# MicroMod-LoRa-1W-Function-Board.net
KiCad netlist of a schematic drawn in EAGLE
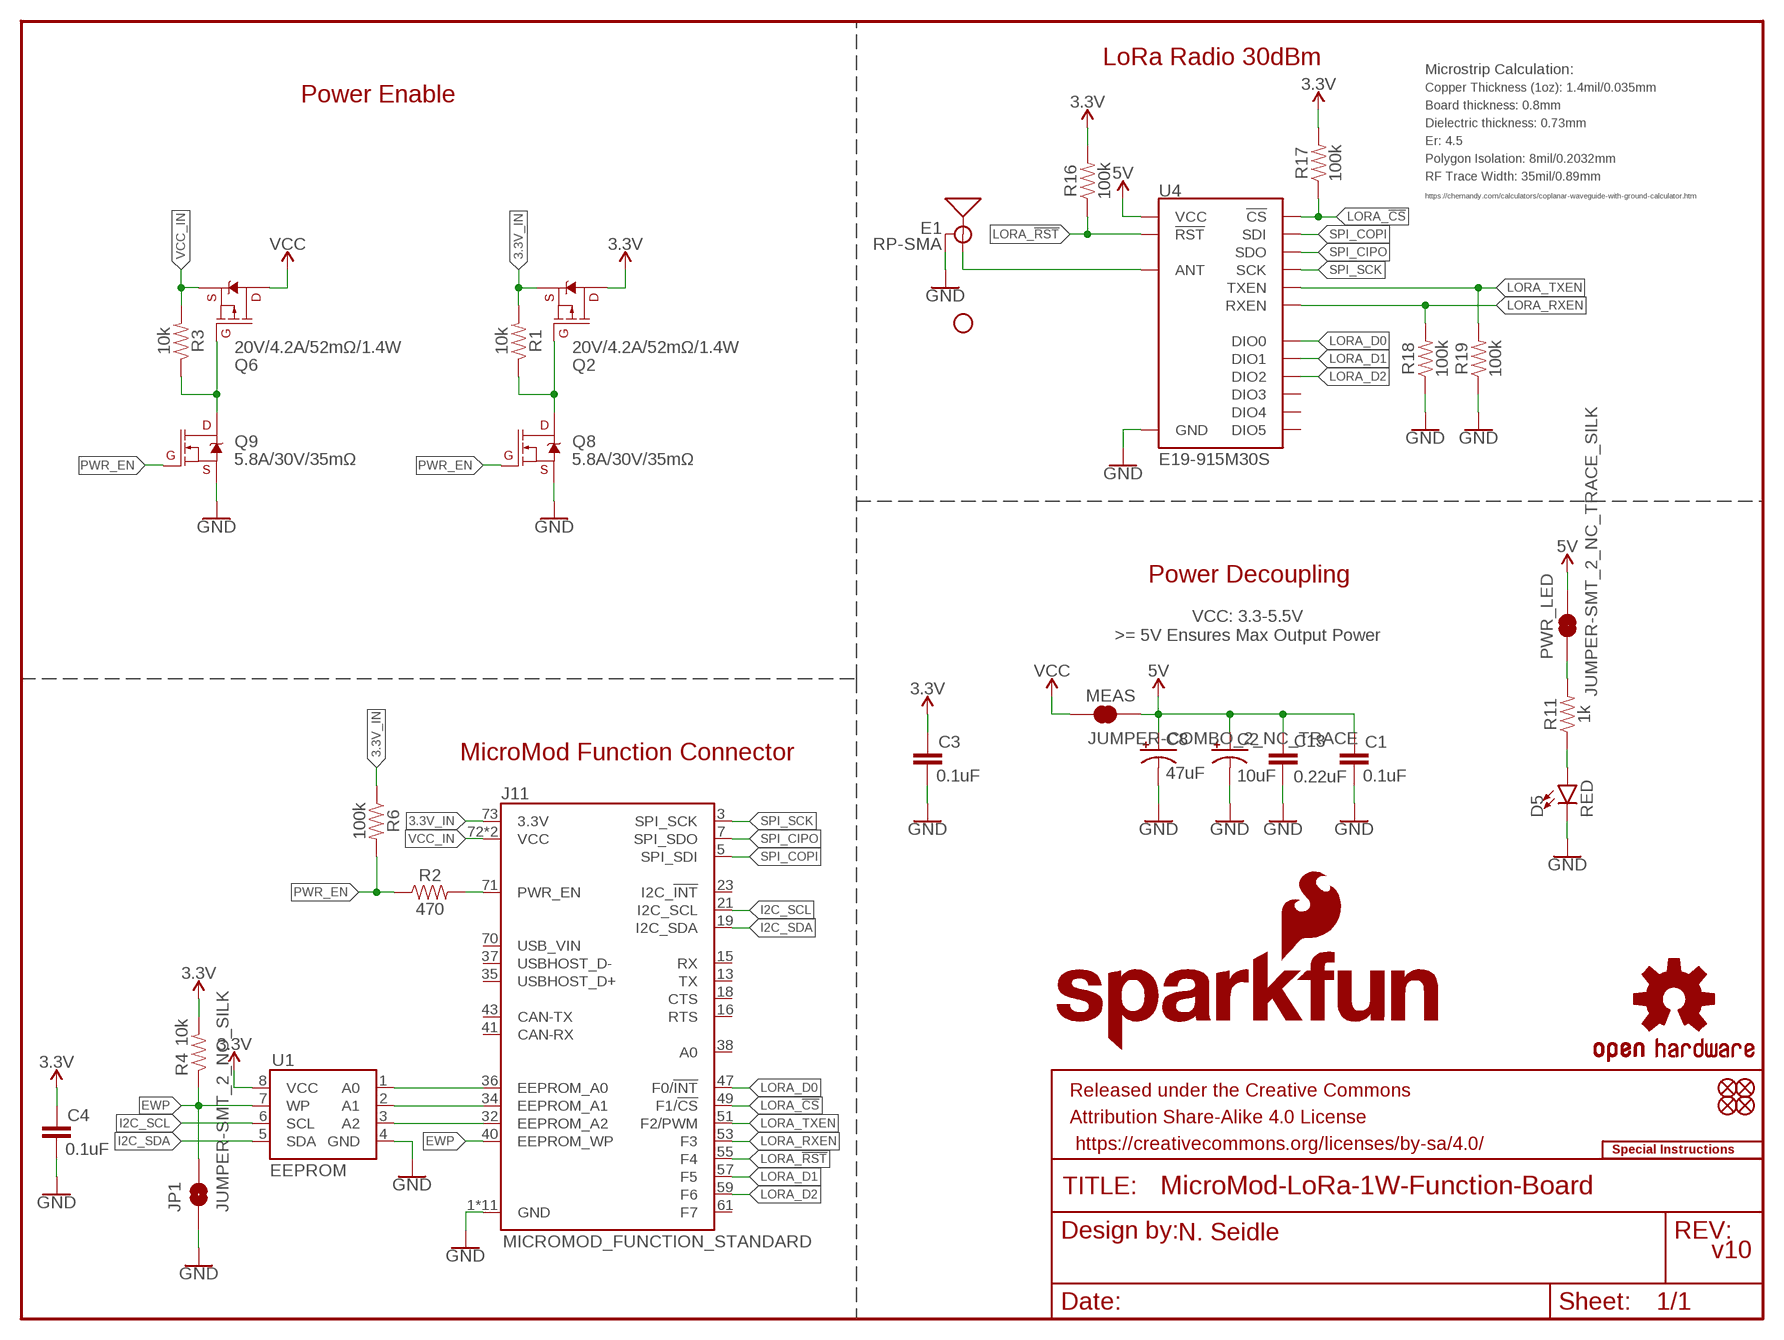
[diagram p0: schematic, sheet 1]

(export (version "E")
  (design (tool "Eeschema 10.0.6"))
  (components
    (comp (ref "C1")
      (value "0.1uF")
      (footprint "eagle-import:0603")
      (libsource (lib "eagle-import") (part "0.1UF-0603-25V-(+80/-20%)"))
    )
    (comp (ref "C2")
      (value "10uF")
      (footprint "eagle-import:EIA3216")
      (libsource (lib "eagle-import") (part "10UF-POLAR-EIA3216-16V-10%(TANT)"))
    )
    (comp (ref "C3")
      (value "0.1uF")
      (footprint "eagle-import:0603")
      (libsource (lib "eagle-import") (part "0.1UF-0603-25V-(+80/-20%)"))
    )
    (comp (ref "C4")
      (value "0.1uF")
      (footprint "eagle-import:0603")
      (libsource (lib "eagle-import") (part "0.1UF-0603-25V-(+80/-20%)"))
    )
    (comp (ref "C8")
      (value "47uF")
      (footprint "eagle-import:EIA3528")
      (libsource (lib "eagle-import") (part "47UF-POLAR-EIA3528-10V-10%"))
    )
    (comp (ref "C13")
      (value "0.22uF")
      (footprint "eagle-import:0603")
      (libsource (lib "eagle-import") (part "0.22UF-0603-25V-10%"))
    )
    (comp (ref "D5")
      (value "RED")
      (footprint "eagle-import:LED-0603")
      (libsource (lib "eagle-import") (part "LED-RED0603"))
    )
    (comp (ref "E1")
      (value "RP-SMA")
      (footprint "eagle-import:SMA-EDGE-SMD")
      (libsource (lib "eagle-import") (part "ANTENNA-SMA-GROUNDEDEDGE_RPSMA_SMD"))
    )
    (comp (ref "FD1")
      (value "FIDUCIALUFIDUCIAL")
      (footprint "eagle-import:FIDUCIAL-MICRO")
      (libsource (lib "eagle-import") (part "FIDUCIALUFIDUCIAL"))
    )
    (comp (ref "FD2")
      (value "FIDUCIALUFIDUCIAL")
      (footprint "eagle-import:FIDUCIAL-MICRO")
      (libsource (lib "eagle-import") (part "FIDUCIALUFIDUCIAL"))
    )
    (comp (ref "FD3")
      (value "FIDUCIALUFIDUCIAL")
      (footprint "eagle-import:FIDUCIAL-MICRO")
      (libsource (lib "eagle-import") (part "FIDUCIALUFIDUCIAL"))
    )
    (comp (ref "FD4")
      (value "FIDUCIALUFIDUCIAL")
      (footprint "eagle-import:FIDUCIAL-MICRO")
      (libsource (lib "eagle-import") (part "FIDUCIALUFIDUCIAL"))
    )
    (comp (ref "FRAME2")
      (value "FRAME-LETTER")
      (footprint "eagle-import:CREATIVE_COMMONS")
      (libsource (lib "eagle-import") (part "FRAME-LETTER"))
    )
    (comp (ref "H1")
      (value "STAND-OFF")
      (footprint "eagle-import:STAND-OFF")
      (libsource (lib "eagle-import") (part "STAND-OFF"))
    )
    (comp (ref "J11")
      (value "MICROMOD_FUNCTION_STANDARD")
      (footprint "eagle-import:M.2-CARD-E-22_FUNCTION_STANDARD")
      (libsource (lib "eagle-import") (part "MICROMOD_FUNCTION_STANDARD"))
    )
    (comp (ref "JP1")
      (value "JUMPER-SMT_2_NO_SILK")
      (footprint "eagle-import:SMT-JUMPER_2_NO_SILK")
      (libsource (lib "eagle-import") (part "JUMPER-SMT_2_NO_SILK"))
    )
    (comp (ref "LOGO1")
      (value "SFE_LOGO_NAME_FLAME.1_INCH")
      (footprint "eagle-import:SFE_LOGO_NAME_FLAME_.1")
      (libsource (lib "eagle-import") (part "SFE_LOGO_NAME_FLAME.1_INCH"))
    )
    (comp (ref "LOGO2")
      (value "SPECIAL_INSTRUCTIONS-ORDERING")
      (footprint "eagle-import:ORDERING_INSTRUCTIONS")
      (libsource (lib "eagle-import") (part "SPECIAL_INSTRUCTIONS-ORDERING"))
    )
    (comp (ref "LOGO3")
      (value "OSHW-LOGOMINI")
      (footprint "eagle-import:OSHW-LOGO-MINI")
      (libsource (lib "eagle-import") (part "OSHW-LOGOMINI"))
    )
    (comp (ref "MEAS")
      (value "JUMPER-COMBO_2_NC_TRACE")
      (footprint "eagle-import:COMBO-JUMPER_2_NC_TRACE")
      (libsource (lib "eagle-import") (part "JUMPER-COMBO_2_NC_TRACE"))
    )
    (comp (ref "PWR_LED")
      (value "JUMPER-SMT_2_NC_TRACE_SILK")
      (footprint "eagle-import:SMT-JUMPER_2_NC_TRACE_SILK")
      (libsource (lib "eagle-import") (part "JUMPER-SMT_2_NC_TRACE_SILK"))
    )
    (comp (ref "Q2")
      (value "20V/4.2A/52mΩ/1.4W")
      (footprint "eagle-import:SOT23-3")
      (libsource (lib "eagle-import") (part "MOSFET_PCH-DMG2305UX-7"))
    )
    (comp (ref "Q6")
      (value "20V/4.2A/52mΩ/1.4W")
      (footprint "eagle-import:SOT23-3")
      (libsource (lib "eagle-import") (part "MOSFET_PCH-DMG2305UX-7"))
    )
    (comp (ref "Q8")
      (value "5.8A/30V/35mΩ")
      (footprint "eagle-import:SOT23-3")
      (libsource (lib "eagle-import") (part "MOSFET-NCH-AO3404A"))
    )
    (comp (ref "Q9")
      (value "5.8A/30V/35mΩ")
      (footprint "eagle-import:SOT23-3")
      (libsource (lib "eagle-import") (part "MOSFET-NCH-AO3404A"))
    )
    (comp (ref "R1")
      (value "10k")
      (footprint "eagle-import:0603")
      (libsource (lib "eagle-import") (part "10KOHM-0603-1/10W-1%"))
    )
    (comp (ref "R2")
      (value "470")
      (footprint "eagle-import:0603")
      (libsource (lib "eagle-import") (part "470OHM-0603-1/10W-1%"))
    )
    (comp (ref "R3")
      (value "10k")
      (footprint "eagle-import:0603")
      (libsource (lib "eagle-import") (part "10KOHM-0603-1/10W-1%"))
    )
    (comp (ref "R4")
      (value "10k")
      (footprint "eagle-import:0603")
      (libsource (lib "eagle-import") (part "10KOHM-0603-1/10W-1%"))
    )
    (comp (ref "R6")
      (value "100k")
      (footprint "eagle-import:0603")
      (libsource (lib "eagle-import") (part "100KOHM-0603-1/10W-1%"))
    )
    (comp (ref "R11")
      (value "1k")
      (footprint "eagle-import:0603")
      (libsource (lib "eagle-import") (part "1KOHM-0603-1/10W-1%"))
    )
    (comp (ref "R16")
      (value "100k")
      (footprint "eagle-import:0603")
      (libsource (lib "eagle-import") (part "100KOHM-0603-1/10W-1%"))
    )
    (comp (ref "R17")
      (value "100k")
      (footprint "eagle-import:0603")
      (libsource (lib "eagle-import") (part "100KOHM-0603-1/10W-1%"))
    )
    (comp (ref "R18")
      (value "100k")
      (footprint "eagle-import:0603")
      (libsource (lib "eagle-import") (part "100KOHM-0603-1/10W-1%"))
    )
    (comp (ref "R19")
      (value "100k")
      (footprint "eagle-import:0603")
      (libsource (lib "eagle-import") (part "100KOHM-0603-1/10W-1%"))
    )
    (comp (ref "U1")
      (value "EEPROM")
      (footprint "eagle-import:SO08")
      (libsource (lib "eagle-import") (part "EEPROM-I2C512K"))
    )
    (comp (ref "U4")
      (value "E19-915M30S")
      (footprint "eagle-import:E19-915MS1W")
      (libsource (lib "eagle-import") (part "E19-915MS1W"))
    )
  )
  (nets
    (net (code "1") (name "/LORA_~{CS}") (class "Default")
      (node (ref "J11") (pin "49") (pinfunction "F1/~{CS}_49") (pintype "bidirectional"))
      (node (ref "R17") (pin "1") (pinfunction "1_1") (pintype "passive"))
      (node (ref "U4") (pin "15") (pinfunction "~{CS}_15") (pintype "bidirectional"))
    )
    (net (code "2") (name "/LORA_~{RST}") (class "Default")
      (node (ref "J11") (pin "55") (pinfunction "F4_55") (pintype "bidirectional"))
      (node (ref "R16") (pin "1") (pinfunction "1_1") (pintype "passive"))
      (node (ref "U4") (pin "8") (pinfunction "~{RST}_8") (pintype "bidirectional"))
    )
    (net (code "3") (name "3.3V") (class "Default")
      (node (ref "C3") (pin "1") (pinfunction "1_1") (pintype "passive"))
      (node (ref "C4") (pin "1") (pinfunction "1_1") (pintype "passive"))
      (node (ref "Q2") (pin "3") (pinfunction "D_3") (pintype "bidirectional"))
      (node (ref "R16") (pin "2") (pinfunction "2_2") (pintype "passive"))
      (node (ref "R17") (pin "2") (pinfunction "2_2") (pintype "passive"))
      (node (ref "R4") (pin "2") (pinfunction "2_2") (pintype "passive"))
      (node (ref "U1") (pin "8") (pinfunction "VCC_8") (pintype "power_in"))
    )
    (net (code "4") (name "3.3V_IN") (class "Default")
      (node (ref "J11") (pin "73") (pinfunction "3.3V_73") (pintype "bidirectional"))
      (node (ref "Q2") (pin "2") (pinfunction "S_2") (pintype "bidirectional"))
      (node (ref "R1") (pin "2") (pinfunction "2_2") (pintype "passive"))
      (node (ref "R6") (pin "1") (pinfunction "1_1") (pintype "passive"))
    )
    (net (code "5") (name "5V") (class "Default")
      (node (ref "C1") (pin "1") (pinfunction "1_1") (pintype "passive"))
      (node (ref "C13") (pin "1") (pinfunction "1_1") (pintype "passive"))
      (node (ref "C2") (pin "+") (pinfunction "+_+") (pintype "passive"))
      (node (ref "C8") (pin "A") (pinfunction "+_A") (pintype "passive"))
      (node (ref "MEAS") (pin "2") (pinfunction "2_2") (pintype "passive"))
      (node (ref "MEAS") (pin "4") (pinfunction "2_4") (pintype "passive"))
      (node (ref "PWR_LED") (pin "2") (pinfunction "2_2") (pintype "passive"))
      (node (ref "U4") (pin "11") (pinfunction "VCC_11") (pintype "bidirectional"))
    )
    (net (code "6") (name "EWP") (class "Default")
      (node (ref "J11") (pin "40") (pinfunction "EEPROM_WP_40") (pintype "bidirectional"))
      (node (ref "JP1") (pin "2") (pinfunction "2_2") (pintype "passive"))
      (node (ref "R4") (pin "1") (pinfunction "1_1") (pintype "passive"))
      (node (ref "U1") (pin "7") (pinfunction "WP_7") (pintype "bidirectional"))
    )
    (net (code "7") (name "GND") (class "Default")
      (node (ref "C1") (pin "2") (pinfunction "2_2") (pintype "passive"))
      (node (ref "C13") (pin "2") (pinfunction "2_2") (pintype "passive"))
      (node (ref "C2") (pin "-") (pinfunction "-_-") (pintype "passive"))
      (node (ref "C3") (pin "2") (pinfunction "2_2") (pintype "passive"))
      (node (ref "C4") (pin "2") (pinfunction "2_2") (pintype "passive"))
      (node (ref "C8") (pin "C") (pinfunction "-_C") (pintype "passive"))
      (node (ref "D5") (pin "C") (pinfunction "C_C") (pintype "passive"))
      (node (ref "E1") (pin "GND@0") (pinfunction "GND_GND@0") (pintype "bidirectional"))
      (node (ref "E1") (pin "GND@1") (pinfunction "GND_GND@1") (pintype "bidirectional"))
      (node (ref "J11") (pin "1") (pinfunction "GND_1") (pintype "bidirectional"))
      (node (ref "J11") (pin "33") (pinfunction "GND_33") (pintype "bidirectional"))
      (node (ref "J11") (pin "39") (pinfunction "GND_39") (pintype "bidirectional"))
      (node (ref "J11") (pin "45") (pinfunction "GND_45") (pintype "bidirectional"))
      (node (ref "J11") (pin "75") (pinfunction "GND_75") (pintype "bidirectional"))
      (node (ref "J11") (pin "GND1") (pinfunction "GND_GND1") (pintype "bidirectional"))
      (node (ref "J11") (pin "GND2") (pinfunction "GND_GND2") (pintype "bidirectional"))
      (node (ref "J11") (pin "GND3") (pinfunction "GND_GND3") (pintype "bidirectional"))
      (node (ref "J11") (pin "GND4") (pinfunction "GND_GND4") (pintype "bidirectional"))
      (node (ref "J11") (pin "GND5") (pinfunction "GND_GND5") (pintype "bidirectional"))
      (node (ref "J11") (pin "GND6") (pinfunction "GND_GND6") (pintype "bidirectional"))
      (node (ref "JP1") (pin "1") (pinfunction "1_1") (pintype "passive"))
      (node (ref "Q8") (pin "2") (pinfunction "S_2") (pintype "bidirectional"))
      (node (ref "Q9") (pin "2") (pinfunction "S_2") (pintype "bidirectional"))
      (node (ref "R18") (pin "1") (pinfunction "1_1") (pintype "passive"))
      (node (ref "R19") (pin "1") (pinfunction "1_1") (pintype "passive"))
      (node (ref "U1") (pin "4") (pinfunction "GND_4") (pintype "power_in"))
      (node (ref "U4") (pin "1") (pinfunction "GND_1") (pintype "bidirectional"))
      (node (ref "U4") (pin "10") (pinfunction "GND_10") (pintype "bidirectional"))
      (node (ref "U4") (pin "18") (pinfunction "GND_18") (pintype "bidirectional"))
      (node (ref "U4") (pin "20") (pinfunction "GND_20") (pintype "bidirectional"))
      (node (ref "U4") (pin "21") (pinfunction "GND_21") (pintype "bidirectional"))
      (node (ref "U4") (pin "22") (pinfunction "GND_22") (pintype "bidirectional"))
      (node (ref "U4") (pin "9") (pinfunction "GND_9") (pintype "bidirectional"))
    )
    (net (code "8") (name "I2C_SCL") (class "Default")
      (node (ref "J11") (pin "21") (pinfunction "I2C_SCL_21") (pintype "bidirectional"))
      (node (ref "U1") (pin "6") (pinfunction "SCL_6") (pintype "bidirectional"))
    )
    (net (code "9") (name "I2C_SDA") (class "Default")
      (node (ref "J11") (pin "19") (pinfunction "I2C_SDA_19") (pintype "bidirectional"))
      (node (ref "U1") (pin "5") (pinfunction "SDA_5") (pintype "bidirectional"))
    )
    (net (code "10") (name "LORA_D0") (class "Default")
      (node (ref "J11") (pin "47") (pinfunction "F0/~{INT}_47") (pintype "bidirectional"))
      (node (ref "U4") (pin "7") (pinfunction "DIO0_7") (pintype "bidirectional"))
    )
    (net (code "11") (name "LORA_D1") (class "Default")
      (node (ref "J11") (pin "57") (pinfunction "F5_57") (pintype "bidirectional"))
      (node (ref "U4") (pin "6") (pinfunction "DIO1_6") (pintype "bidirectional"))
    )
    (net (code "12") (name "LORA_D2") (class "Default")
      (node (ref "J11") (pin "59") (pinfunction "F6_59") (pintype "bidirectional"))
      (node (ref "U4") (pin "5") (pinfunction "DIO2_5") (pintype "bidirectional"))
    )
    (net (code "13") (name "LORA_RXEN") (class "Default")
      (node (ref "J11") (pin "53") (pinfunction "F3_53") (pintype "bidirectional"))
      (node (ref "R18") (pin "2") (pinfunction "2_2") (pintype "passive"))
      (node (ref "U4") (pin "17") (pinfunction "RXEN_17") (pintype "bidirectional"))
    )
    (net (code "14") (name "LORA_TXEN") (class "Default")
      (node (ref "J11") (pin "51") (pinfunction "F2/PWM_51") (pintype "bidirectional"))
      (node (ref "R19") (pin "2") (pinfunction "2_2") (pintype "passive"))
      (node (ref "U4") (pin "16") (pinfunction "TXEN_16") (pintype "bidirectional"))
    )
    (net (code "15") (name "Net-(D5-PadA)") (class "Default")
      (node (ref "D5") (pin "A") (pinfunction "A_A") (pintype "passive"))
      (node (ref "R11") (pin "1") (pinfunction "1_1") (pintype "passive"))
    )
    (net (code "16") (name "Net-(E1-SIGNAL)") (class "Default")
      (node (ref "E1") (pin "SIG") (pinfunction "SIGNAL_SIG") (pintype "bidirectional"))
      (node (ref "U4") (pin "19") (pinfunction "ANT_19") (pintype "bidirectional"))
    )
    (net (code "17") (name "Net-(J11-EEPROM_A0)") (class "Default")
      (node (ref "J11") (pin "36") (pinfunction "EEPROM_A0_36") (pintype "bidirectional"))
      (node (ref "U1") (pin "1") (pinfunction "A0_1") (pintype "bidirectional"))
    )
    (net (code "18") (name "Net-(J11-EEPROM_A1)") (class "Default")
      (node (ref "J11") (pin "34") (pinfunction "EEPROM_A1_34") (pintype "bidirectional"))
      (node (ref "U1") (pin "2") (pinfunction "A1_2") (pintype "bidirectional"))
    )
    (net (code "19") (name "Net-(J11-EEPROM_A2)") (class "Default")
      (node (ref "J11") (pin "32") (pinfunction "EEPROM_A2_32") (pintype "bidirectional"))
      (node (ref "U1") (pin "3") (pinfunction "A2_3") (pintype "bidirectional"))
    )
    (net (code "20") (name "Net-(J11-PWR_EN)") (class "Default")
      (node (ref "J11") (pin "71") (pinfunction "PWR_EN_71") (pintype "bidirectional"))
      (node (ref "R2") (pin "2") (pinfunction "2_2") (pintype "passive"))
    )
    (net (code "21") (name "Net-(PWR_LED-Pad1)") (class "Default")
      (node (ref "PWR_LED") (pin "1") (pinfunction "1_1") (pintype "passive"))
      (node (ref "R11") (pin "2") (pinfunction "2_2") (pintype "passive"))
    )
    (net (code "22") (name "Net-(Q2-G)") (class "Default")
      (node (ref "Q2") (pin "1") (pinfunction "G_1") (pintype "bidirectional"))
      (node (ref "Q8") (pin "3") (pinfunction "D_3") (pintype "bidirectional"))
      (node (ref "R1") (pin "1") (pinfunction "1_1") (pintype "passive"))
    )
    (net (code "23") (name "Net-(Q6-G)") (class "Default")
      (node (ref "Q6") (pin "1") (pinfunction "G_1") (pintype "bidirectional"))
      (node (ref "Q9") (pin "3") (pinfunction "D_3") (pintype "bidirectional"))
      (node (ref "R3") (pin "1") (pinfunction "1_1") (pintype "passive"))
    )
    (net (code "24") (name "PWR_EN") (class "Default")
      (node (ref "Q8") (pin "1") (pinfunction "G_1") (pintype "bidirectional"))
      (node (ref "Q9") (pin "1") (pinfunction "G_1") (pintype "bidirectional"))
      (node (ref "R2") (pin "1") (pinfunction "1_1") (pintype "passive"))
      (node (ref "R6") (pin "2") (pinfunction "2_2") (pintype "passive"))
    )
    (net (code "25") (name "SPI_CIPO") (class "Default")
      (node (ref "J11") (pin "7") (pinfunction "SPI_SDO_7") (pintype "bidirectional"))
      (node (ref "U4") (pin "13") (pinfunction "SDO_13") (pintype "bidirectional"))
    )
    (net (code "26") (name "SPI_COPI") (class "Default")
      (node (ref "J11") (pin "5") (pinfunction "SPI_SDI_5") (pintype "bidirectional"))
      (node (ref "U4") (pin "14") (pinfunction "SDI_14") (pintype "bidirectional"))
    )
    (net (code "27") (name "SPI_SCK") (class "Default")
      (node (ref "J11") (pin "3") (pinfunction "SPI_SCK_3") (pintype "bidirectional"))
      (node (ref "U4") (pin "12") (pinfunction "SCK_12") (pintype "bidirectional"))
    )
    (net (code "28") (name "VCC") (class "Default")
      (node (ref "MEAS") (pin "1") (pinfunction "1_1") (pintype "passive"))
      (node (ref "MEAS") (pin "3") (pinfunction "1_3") (pintype "passive"))
      (node (ref "Q6") (pin "3") (pinfunction "D_3") (pintype "bidirectional"))
    )
    (net (code "29") (name "VCC_IN") (class "Default")
      (node (ref "J11") (pin "72") (pinfunction "VCC_72") (pintype "bidirectional"))
      (node (ref "J11") (pin "74") (pinfunction "VCC_74") (pintype "bidirectional"))
      (node (ref "Q6") (pin "2") (pinfunction "S_2") (pintype "bidirectional"))
      (node (ref "R3") (pin "2") (pinfunction "2_2") (pintype "passive"))
    )
    (net (code "30") (name "unconnected-(J11-A0-Pad38)") (class "Default")
      (node (ref "J11") (pin "38") (pinfunction "A0_38") (pintype "bidirectional"))
    )
    (net (code "31") (name "unconnected-(J11-CAN-RX-Pad41)") (class "Default")
      (node (ref "J11") (pin "41") (pinfunction "CAN-RX_41") (pintype "bidirectional"))
    )
    (net (code "32") (name "unconnected-(J11-CAN-TX-Pad43)") (class "Default")
      (node (ref "J11") (pin "43") (pinfunction "CAN-TX_43") (pintype "bidirectional"))
    )
    (net (code "33") (name "unconnected-(J11-CTS-Pad18)") (class "Default")
      (node (ref "J11") (pin "18") (pinfunction "CTS_18") (pintype "bidirectional"))
    )
    (net (code "34") (name "unconnected-(J11-F7-Pad61)") (class "Default")
      (node (ref "J11") (pin "61") (pinfunction "F7_61") (pintype "bidirectional"))
    )
    (net (code "35") (name "unconnected-(J11-I2C_~{INT}-Pad23)") (class "Default")
      (node (ref "J11") (pin "23") (pinfunction "I2C_~{INT}_23") (pintype "bidirectional"))
    )
    (net (code "36") (name "unconnected-(J11-RTS-Pad16)") (class "Default")
      (node (ref "J11") (pin "16") (pinfunction "RTS_16") (pintype "bidirectional"))
    )
    (net (code "37") (name "unconnected-(J11-RX-Pad15)") (class "Default")
      (node (ref "J11") (pin "15") (pinfunction "RX_15") (pintype "bidirectional"))
    )
    (net (code "38") (name "unconnected-(J11-TX-Pad13)") (class "Default")
      (node (ref "J11") (pin "13") (pinfunction "TX_13") (pintype "bidirectional"))
    )
    (net (code "39") (name "unconnected-(J11-USBHOST_D+-Pad35)") (class "Default")
      (node (ref "J11") (pin "35") (pinfunction "USBHOST_D+_35") (pintype "bidirectional"))
    )
    (net (code "40") (name "unconnected-(J11-USBHOST_D--Pad37)") (class "Default")
      (node (ref "J11") (pin "37") (pinfunction "USBHOST_D-_37") (pintype "bidirectional"))
    )
    (net (code "41") (name "unconnected-(J11-USB_VIN-Pad70)") (class "Default")
      (node (ref "J11") (pin "70") (pinfunction "USB_VIN_70") (pintype "bidirectional"))
    )
    (net (code "42") (name "unconnected-(U4-DIO3-Pad4)") (class "Default")
      (node (ref "U4") (pin "4") (pinfunction "DIO3_4") (pintype "bidirectional"))
    )
    (net (code "43") (name "unconnected-(U4-DIO4-Pad3)") (class "Default")
      (node (ref "U4") (pin "3") (pinfunction "DIO4_3") (pintype "bidirectional"))
    )
    (net (code "44") (name "unconnected-(U4-DIO5-Pad2)") (class "Default")
      (node (ref "U4") (pin "2") (pinfunction "DIO5_2") (pintype "bidirectional"))
    )
  )
)
